# Relay2_Block.net
KiCad netlist of a schematic drawn in Altium Designer
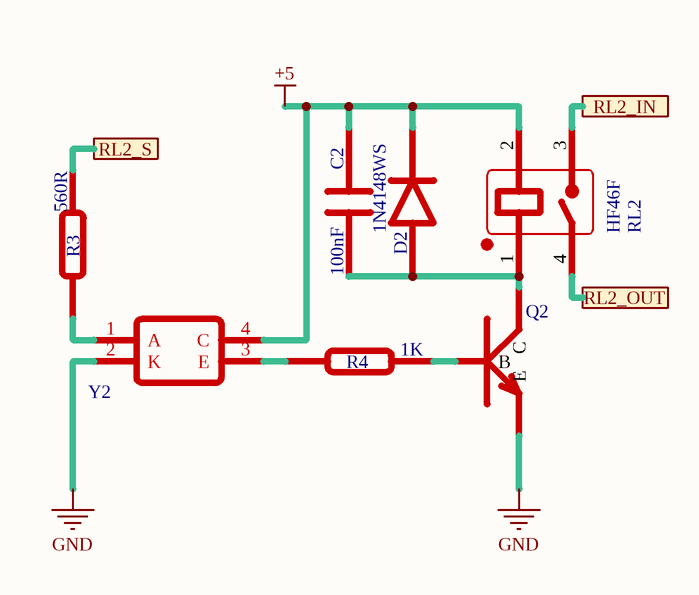
[diagram p0: Relay2_Block.SchDoc]

(export (version "E")
  (design (tool "Eeschema 10.0.6"))
  (components
    (comp (ref "C2")
      (value "100nF")
      (footprint "C0805")
      (description "Ceramic Capacitor")
      (libsource (lib "CTAI-Library") (part "CAP-CER"))
    )
    (comp (ref "D2")
      (value "1N4148WS")
      (footprint "SMA")
      (description "Small Signal Diode")
      (libsource (lib "CTAI-Library") (part "1N4148WS"))
    )
    (comp (ref "Q2")
      (value "S8050")
      (footprint "SOT-23")
      (description "NPN Transistors 0.5A Collector to Emitter 25V")
      (libsource (lib "CTAI-Library") (part "S8050"))
    )
    (comp (ref "R3")
      (value "560R")
      (footprint "R0603")
      (description "Resistor")
      (libsource (lib "CTAI-Library") (part "Resistor"))
    )
    (comp (ref "R4")
      (value "1K")
      (footprint "R0603")
      (description "Resistor")
      (libsource (lib "CTAI-Library") (part "Resistor"))
    )
    (comp (ref "RL2")
      (value "HF46F")
      (footprint "HF-46-X")
      (description "Relay 4 Pin")
      (libsource (lib "CTAI-Library") (part "HF46F"))
    )
    (comp (ref "Y2")
      (value "PHOTOCOUPLER")
      (footprint "SOP-4")
      (description "Photo-Coupler")
      (libsource (lib "CTAI-Library") (part "PC817"))
    )
  )
  (nets
    (net (code "1") (name "+5") (class "Default")
      (node (ref "C2") (pin "2") (pintype "passive"))
      (node (ref "D2") (pin "K") (pinfunction "K_K") (pintype "passive"))
      (node (ref "RL2") (pin "2") (pinfunction "2_2") (pintype "passive"))
      (node (ref "Y2") (pin "4") (pinfunction "C_4") (pintype "passive"))
    )
    (net (code "2") (name "/RL2_IN") (class "Default")
      (node (ref "RL2") (pin "3") (pinfunction "3_3") (pintype "passive"))
    )
    (net (code "3") (name "/RL2_OUT") (class "Default")
      (node (ref "RL2") (pin "4") (pinfunction "4_4") (pintype "passive"))
    )
    (net (code "4") (name "/RL2_S") (class "Default")
      (node (ref "R3") (pin "1") (pinfunction "1_1") (pintype "passive"))
    )
    (net (code "5") (name "GND") (class "Default")
      (node (ref "Q2") (pin "2") (pinfunction "E_2") (pintype "passive"))
      (node (ref "Y2") (pin "2") (pinfunction "K_2") (pintype "passive"))
    )
    (net (code "6") (name "Net-(Q2-B)") (class "Default")
      (node (ref "Q2") (pin "1") (pinfunction "B_1") (pintype "passive"))
      (node (ref "R4") (pin "1") (pinfunction "1_1") (pintype "passive"))
    )
    (net (code "7") (name "Net-(Q2-C)") (class "Default")
      (node (ref "C2") (pin "1") (pintype "passive"))
      (node (ref "D2") (pin "A") (pinfunction "A_A") (pintype "passive"))
      (node (ref "Q2") (pin "3") (pinfunction "C_3") (pintype "passive"))
      (node (ref "RL2") (pin "1") (pinfunction "1_1") (pintype "passive"))
    )
    (net (code "8") (name "Net-(Y2-A)") (class "Default")
      (node (ref "R3") (pin "2") (pinfunction "2_2") (pintype "passive"))
      (node (ref "Y2") (pin "1") (pinfunction "A_1") (pintype "passive"))
    )
    (net (code "9") (name "Net-(Y2-E)") (class "Default")
      (node (ref "R4") (pin "2") (pinfunction "2_2") (pintype "passive"))
      (node (ref "Y2") (pin "3") (pinfunction "E_3") (pintype "passive"))
    )
  )
)
